# SCH_DrumSet_2024-08-07.net
KiCad netlist of a schematic drawn in EasyEDA
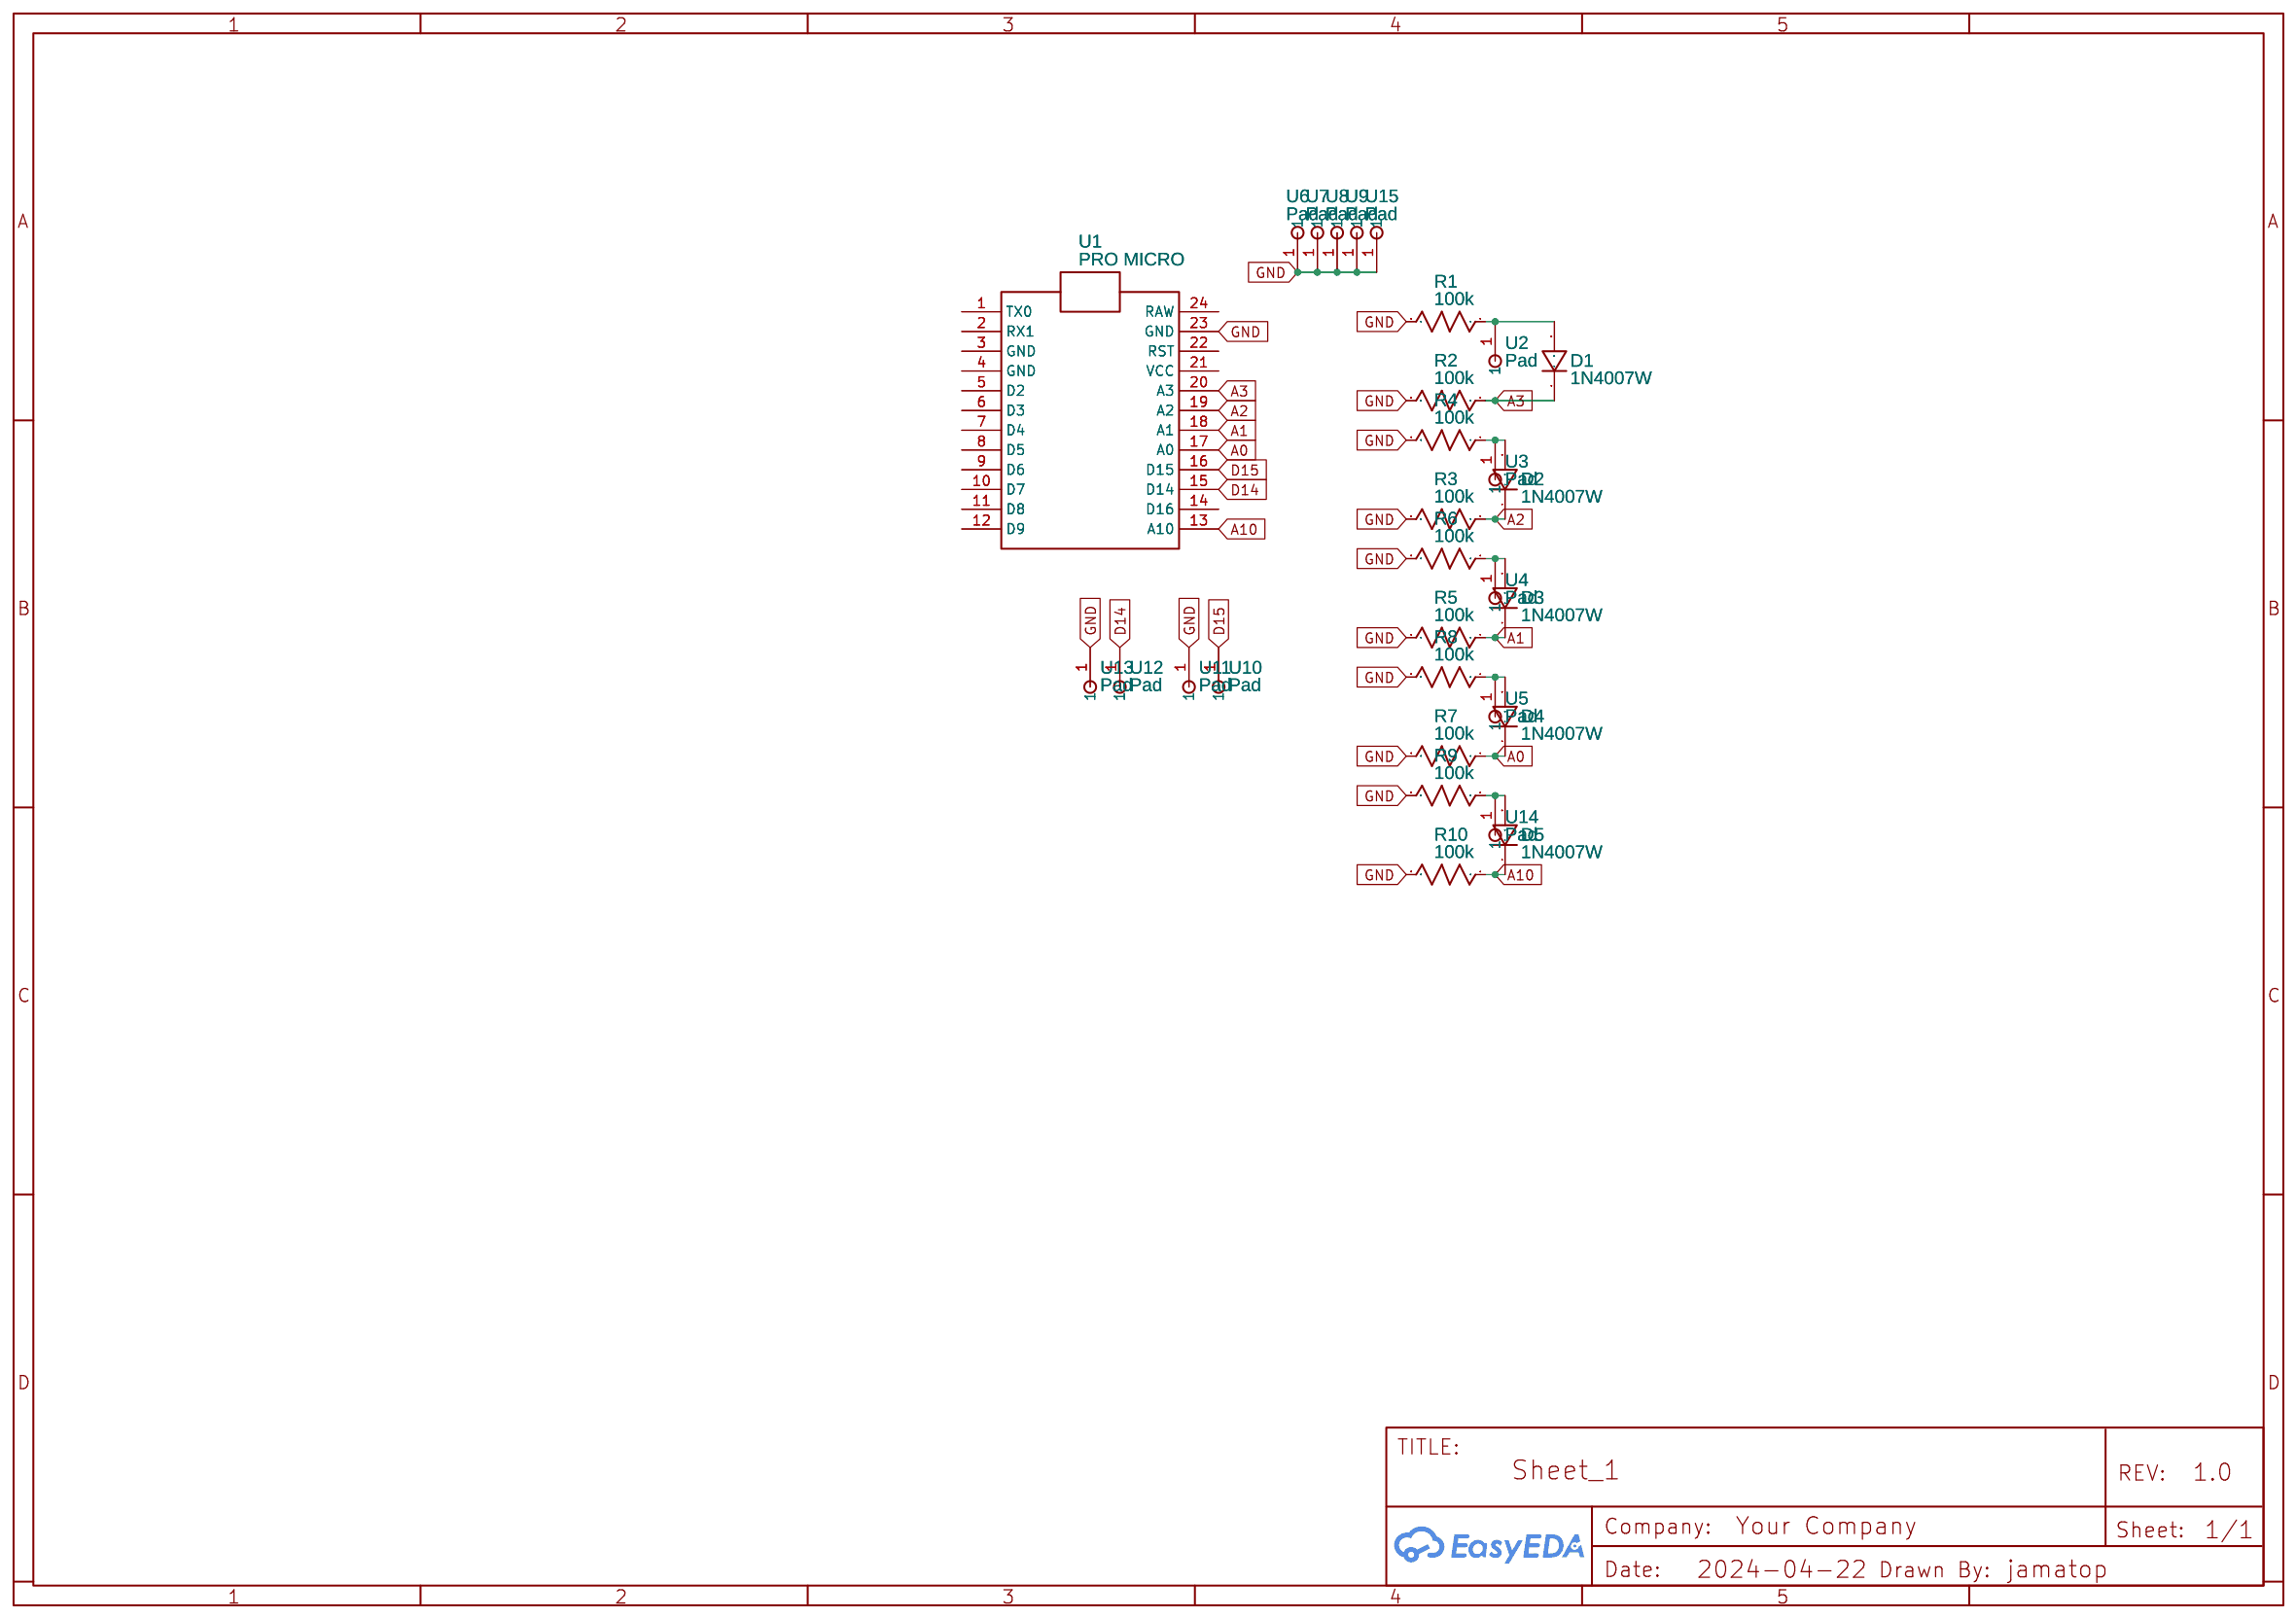
[diagram p0: schematic sheet]

(export (version "E")
  (design (tool "Eeschema 10.0.6"))
  (components
    (comp (ref "D1")
      (value "1N4007W")
      (fields (field (name "Manufacturer") "BLUE ROCKET"))
      (libsource (lib "") (part "1N4007W"))
    )
    (comp (ref "D2")
      (value "1N4007W")
      (fields (field (name "Manufacturer") "BLUE ROCKET"))
      (libsource (lib "") (part "1N4007W"))
    )
    (comp (ref "D3")
      (value "1N4007W")
      (fields (field (name "Manufacturer") "BLUE ROCKET"))
      (libsource (lib "") (part "1N4007W"))
    )
    (comp (ref "D4")
      (value "1N4007W")
      (fields (field (name "Manufacturer") "BLUE ROCKET"))
      (libsource (lib "") (part "1N4007W"))
    )
    (comp (ref "D5")
      (value "1N4007W")
      (fields (field (name "Manufacturer") "BLUE ROCKET"))
      (libsource (lib "") (part "1N4007W"))
    )
    (comp (ref "R1") (value "100k") (libsource (lib "") (part "R_0603_US")))
    (comp (ref "R2") (value "100k") (libsource (lib "") (part "R_0603_US")))
    (comp (ref "R3") (value "100k") (libsource (lib "") (part "R_0603_US")))
    (comp (ref "R4") (value "100k") (libsource (lib "") (part "R_0603_US")))
    (comp (ref "R5") (value "100k") (libsource (lib "") (part "R_0603_US")))
    (comp (ref "R6") (value "100k") (libsource (lib "") (part "R_0603_US")))
    (comp (ref "R7") (value "100k") (libsource (lib "") (part "R_0603_US")))
    (comp (ref "R8") (value "100k") (libsource (lib "") (part "R_0603_US")))
    (comp (ref "R9") (value "100k") (libsource (lib "") (part "R_0603_US")))
    (comp (ref "R10") (value "100k") (libsource (lib "") (part "R_0603_US")))
    (comp (ref "U1") (value "PRO MICRO") (libsource (lib "") (part "PRO MICRO")))
    (comp (ref "U2")
      (value "Pad")
      (fields (field (name "Manufacturer Part") "AdamsPads"))
      (libsource (lib "") (part "Pad_1"))
    )
    (comp (ref "U3")
      (value "Pad")
      (fields (field (name "Manufacturer Part") "AdamsPads"))
      (libsource (lib "") (part "Pad_1"))
    )
    (comp (ref "U4")
      (value "Pad")
      (fields (field (name "Manufacturer Part") "AdamsPads"))
      (libsource (lib "") (part "Pad_1"))
    )
    (comp (ref "U5")
      (value "Pad")
      (fields (field (name "Manufacturer Part") "AdamsPads"))
      (libsource (lib "") (part "Pad_1"))
    )
    (comp (ref "U6")
      (value "Pad")
      (fields (field (name "Manufacturer Part") "AdamsPads"))
      (libsource (lib "") (part "Pad"))
    )
    (comp (ref "U7")
      (value "Pad")
      (fields (field (name "Manufacturer Part") "AdamsPads"))
      (libsource (lib "") (part "Pad"))
    )
    (comp (ref "U8")
      (value "Pad")
      (fields (field (name "Manufacturer Part") "AdamsPads"))
      (libsource (lib "") (part "Pad"))
    )
    (comp (ref "U9")
      (value "Pad")
      (fields (field (name "Manufacturer Part") "AdamsPads"))
      (libsource (lib "") (part "Pad"))
    )
    (comp (ref "U10")
      (value "Pad")
      (fields (field (name "Manufacturer Part") "AdamsPads"))
      (libsource (lib "") (part "Pad_1"))
    )
    (comp (ref "U11")
      (value "Pad")
      (fields (field (name "Manufacturer Part") "AdamsPads"))
      (libsource (lib "") (part "Pad_1"))
    )
    (comp (ref "U12")
      (value "Pad")
      (fields (field (name "Manufacturer Part") "AdamsPads"))
      (libsource (lib "") (part "Pad_1"))
    )
    (comp (ref "U13")
      (value "Pad")
      (fields (field (name "Manufacturer Part") "AdamsPads"))
      (libsource (lib "") (part "Pad_1"))
    )
    (comp (ref "U14")
      (value "Pad")
      (fields (field (name "Manufacturer Part") "AdamsPads"))
      (libsource (lib "") (part "Pad_1"))
    )
    (comp (ref "U15")
      (value "Pad")
      (fields (field (name "Manufacturer Part") "AdamsPads"))
      (libsource (lib "") (part "Pad"))
    )
  )
  (nets
    (net (code "1") (name "A0") (class "Default")
      (node (ref "D4") (pin "1") (pinfunction "1_1") (pintype "unspecified"))
      (node (ref "R7") (pin "1") (pinfunction "1_1") (pintype "unspecified"))
      (node (ref "U1") (pin "17") (pinfunction "A0_17") (pintype "unspecified"))
    )
    (net (code "2") (name "A1") (class "Default")
      (node (ref "D3") (pin "1") (pinfunction "1_1") (pintype "unspecified"))
      (node (ref "R5") (pin "1") (pinfunction "1_1") (pintype "unspecified"))
      (node (ref "U1") (pin "18") (pinfunction "A1_18") (pintype "unspecified"))
    )
    (net (code "3") (name "A2") (class "Default")
      (node (ref "D2") (pin "1") (pinfunction "1_1") (pintype "unspecified"))
      (node (ref "R3") (pin "1") (pinfunction "1_1") (pintype "unspecified"))
      (node (ref "U1") (pin "19") (pinfunction "A2_19") (pintype "unspecified"))
    )
    (net (code "4") (name "A3") (class "Default")
      (node (ref "D1") (pin "1") (pinfunction "1_1") (pintype "unspecified"))
      (node (ref "R2") (pin "1") (pinfunction "1_1") (pintype "unspecified"))
      (node (ref "U1") (pin "20") (pinfunction "A3_20") (pintype "unspecified"))
    )
    (net (code "5") (name "A10") (class "Default")
      (node (ref "D5") (pin "1") (pinfunction "1_1") (pintype "unspecified"))
      (node (ref "R10") (pin "1") (pinfunction "1_1") (pintype "unspecified"))
      (node (ref "U1") (pin "13") (pinfunction "A10_13") (pintype "unspecified"))
    )
    (net (code "6") (name "D14") (class "Default")
      (node (ref "U1") (pin "15") (pinfunction "D14_15") (pintype "unspecified"))
      (node (ref "U12") (pin "1") (pinfunction "1_1") (pintype "unspecified"))
    )
    (net (code "7") (name "D15") (class "Default")
      (node (ref "U1") (pin "16") (pinfunction "D15_16") (pintype "unspecified"))
      (node (ref "U10") (pin "1") (pinfunction "1_1") (pintype "unspecified"))
    )
    (net (code "8") (name "GND") (class "Default")
      (node (ref "R1") (pin "2") (pinfunction "2_2") (pintype "unspecified"))
      (node (ref "R10") (pin "2") (pinfunction "2_2") (pintype "unspecified"))
      (node (ref "R2") (pin "2") (pinfunction "2_2") (pintype "unspecified"))
      (node (ref "R3") (pin "2") (pinfunction "2_2") (pintype "unspecified"))
      (node (ref "R4") (pin "2") (pinfunction "2_2") (pintype "unspecified"))
      (node (ref "R5") (pin "2") (pinfunction "2_2") (pintype "unspecified"))
      (node (ref "R6") (pin "2") (pinfunction "2_2") (pintype "unspecified"))
      (node (ref "R7") (pin "2") (pinfunction "2_2") (pintype "unspecified"))
      (node (ref "R8") (pin "2") (pinfunction "2_2") (pintype "unspecified"))
      (node (ref "R9") (pin "2") (pinfunction "2_2") (pintype "unspecified"))
      (node (ref "U1") (pin "23") (pinfunction "GND_23") (pintype "unspecified"))
      (node (ref "U11") (pin "1") (pinfunction "1_1") (pintype "unspecified"))
      (node (ref "U13") (pin "1") (pinfunction "1_1") (pintype "unspecified"))
      (node (ref "U15") (pin "1") (pinfunction "1_1") (pintype "unspecified"))
      (node (ref "U6") (pin "1") (pinfunction "1_1") (pintype "unspecified"))
      (node (ref "U7") (pin "1") (pinfunction "1_1") (pintype "unspecified"))
      (node (ref "U8") (pin "1") (pinfunction "1_1") (pintype "unspecified"))
      (node (ref "U9") (pin "1") (pinfunction "1_1") (pintype "unspecified"))
    )
    (net (code "9") (name "Net-(D1-Pad2)") (class "Default")
      (node (ref "D1") (pin "2") (pinfunction "2_2") (pintype "unspecified"))
      (node (ref "R1") (pin "1") (pinfunction "1_1") (pintype "unspecified"))
      (node (ref "U2") (pin "1") (pinfunction "1_1") (pintype "unspecified"))
    )
    (net (code "10") (name "Net-(D2-Pad2)") (class "Default")
      (node (ref "D2") (pin "2") (pinfunction "2_2") (pintype "unspecified"))
      (node (ref "R4") (pin "1") (pinfunction "1_1") (pintype "unspecified"))
      (node (ref "U3") (pin "1") (pinfunction "1_1") (pintype "unspecified"))
    )
    (net (code "11") (name "Net-(D3-Pad2)") (class "Default")
      (node (ref "D3") (pin "2") (pinfunction "2_2") (pintype "unspecified"))
      (node (ref "R6") (pin "1") (pinfunction "1_1") (pintype "unspecified"))
      (node (ref "U4") (pin "1") (pinfunction "1_1") (pintype "unspecified"))
    )
    (net (code "12") (name "Net-(D4-Pad2)") (class "Default")
      (node (ref "D4") (pin "2") (pinfunction "2_2") (pintype "unspecified"))
      (node (ref "R8") (pin "1") (pinfunction "1_1") (pintype "unspecified"))
      (node (ref "U5") (pin "1") (pinfunction "1_1") (pintype "unspecified"))
    )
    (net (code "13") (name "Net-(D5-Pad2)") (class "Default")
      (node (ref "D5") (pin "2") (pinfunction "2_2") (pintype "unspecified"))
      (node (ref "R9") (pin "1") (pinfunction "1_1") (pintype "unspecified"))
      (node (ref "U14") (pin "1") (pinfunction "1_1") (pintype "unspecified"))
    )
    (net (code "14") (name "unconnected-(U1-D2-Pad5)") (class "Default")
      (node (ref "U1") (pin "5") (pinfunction "D2_5") (pintype "unspecified"))
    )
    (net (code "15") (name "unconnected-(U1-D3-Pad6)") (class "Default")
      (node (ref "U1") (pin "6") (pinfunction "D3_6") (pintype "unspecified"))
    )
    (net (code "16") (name "unconnected-(U1-D4-Pad7)") (class "Default")
      (node (ref "U1") (pin "7") (pinfunction "D4_7") (pintype "unspecified"))
    )
    (net (code "17") (name "unconnected-(U1-D5-Pad8)") (class "Default")
      (node (ref "U1") (pin "8") (pinfunction "D5_8") (pintype "unspecified"))
    )
    (net (code "18") (name "unconnected-(U1-D6-Pad9)") (class "Default")
      (node (ref "U1") (pin "9") (pinfunction "D6_9") (pintype "unspecified"))
    )
    (net (code "19") (name "unconnected-(U1-D7-Pad10)") (class "Default")
      (node (ref "U1") (pin "10") (pinfunction "D7_10") (pintype "unspecified"))
    )
    (net (code "20") (name "unconnected-(U1-D8-Pad11)") (class "Default")
      (node (ref "U1") (pin "11") (pinfunction "D8_11") (pintype "unspecified"))
    )
    (net (code "21") (name "unconnected-(U1-D9-Pad12)") (class "Default")
      (node (ref "U1") (pin "12") (pinfunction "D9_12") (pintype "unspecified"))
    )
    (net (code "22") (name "unconnected-(U1-D16-Pad14)") (class "Default")
      (node (ref "U1") (pin "14") (pinfunction "D16_14") (pintype "unspecified"))
    )
    (net (code "23") (name "unconnected-(U1-GND-Pad3)") (class "Default")
      (node (ref "U1") (pin "3") (pinfunction "GND_3") (pintype "unspecified"))
    )
    (net (code "24") (name "unconnected-(U1-GND-Pad4)") (class "Default")
      (node (ref "U1") (pin "4") (pinfunction "GND_4") (pintype "unspecified"))
    )
    (net (code "25") (name "unconnected-(U1-RAW-Pad24)") (class "Default")
      (node (ref "U1") (pin "24") (pinfunction "RAW_24") (pintype "unspecified"))
    )
    (net (code "26") (name "unconnected-(U1-RST-Pad22)") (class "Default")
      (node (ref "U1") (pin "22") (pinfunction "RST_22") (pintype "unspecified"))
    )
    (net (code "27") (name "unconnected-(U1-RX1-Pad2)") (class "Default")
      (node (ref "U1") (pin "2") (pinfunction "RX1_2") (pintype "unspecified"))
    )
    (net (code "28") (name "unconnected-(U1-TX0-Pad1)") (class "Default")
      (node (ref "U1") (pin "1") (pinfunction "TX0_1") (pintype "unspecified"))
    )
    (net (code "29") (name "unconnected-(U1-VCC-Pad21)") (class "Default")
      (node (ref "U1") (pin "21") (pinfunction "VCC_21") (pintype "unspecified"))
    )
  )
)
